# SCH_Mini_Fridge_Hat_2022-05-06.net
KiCad netlist of a schematic drawn in EasyEDA
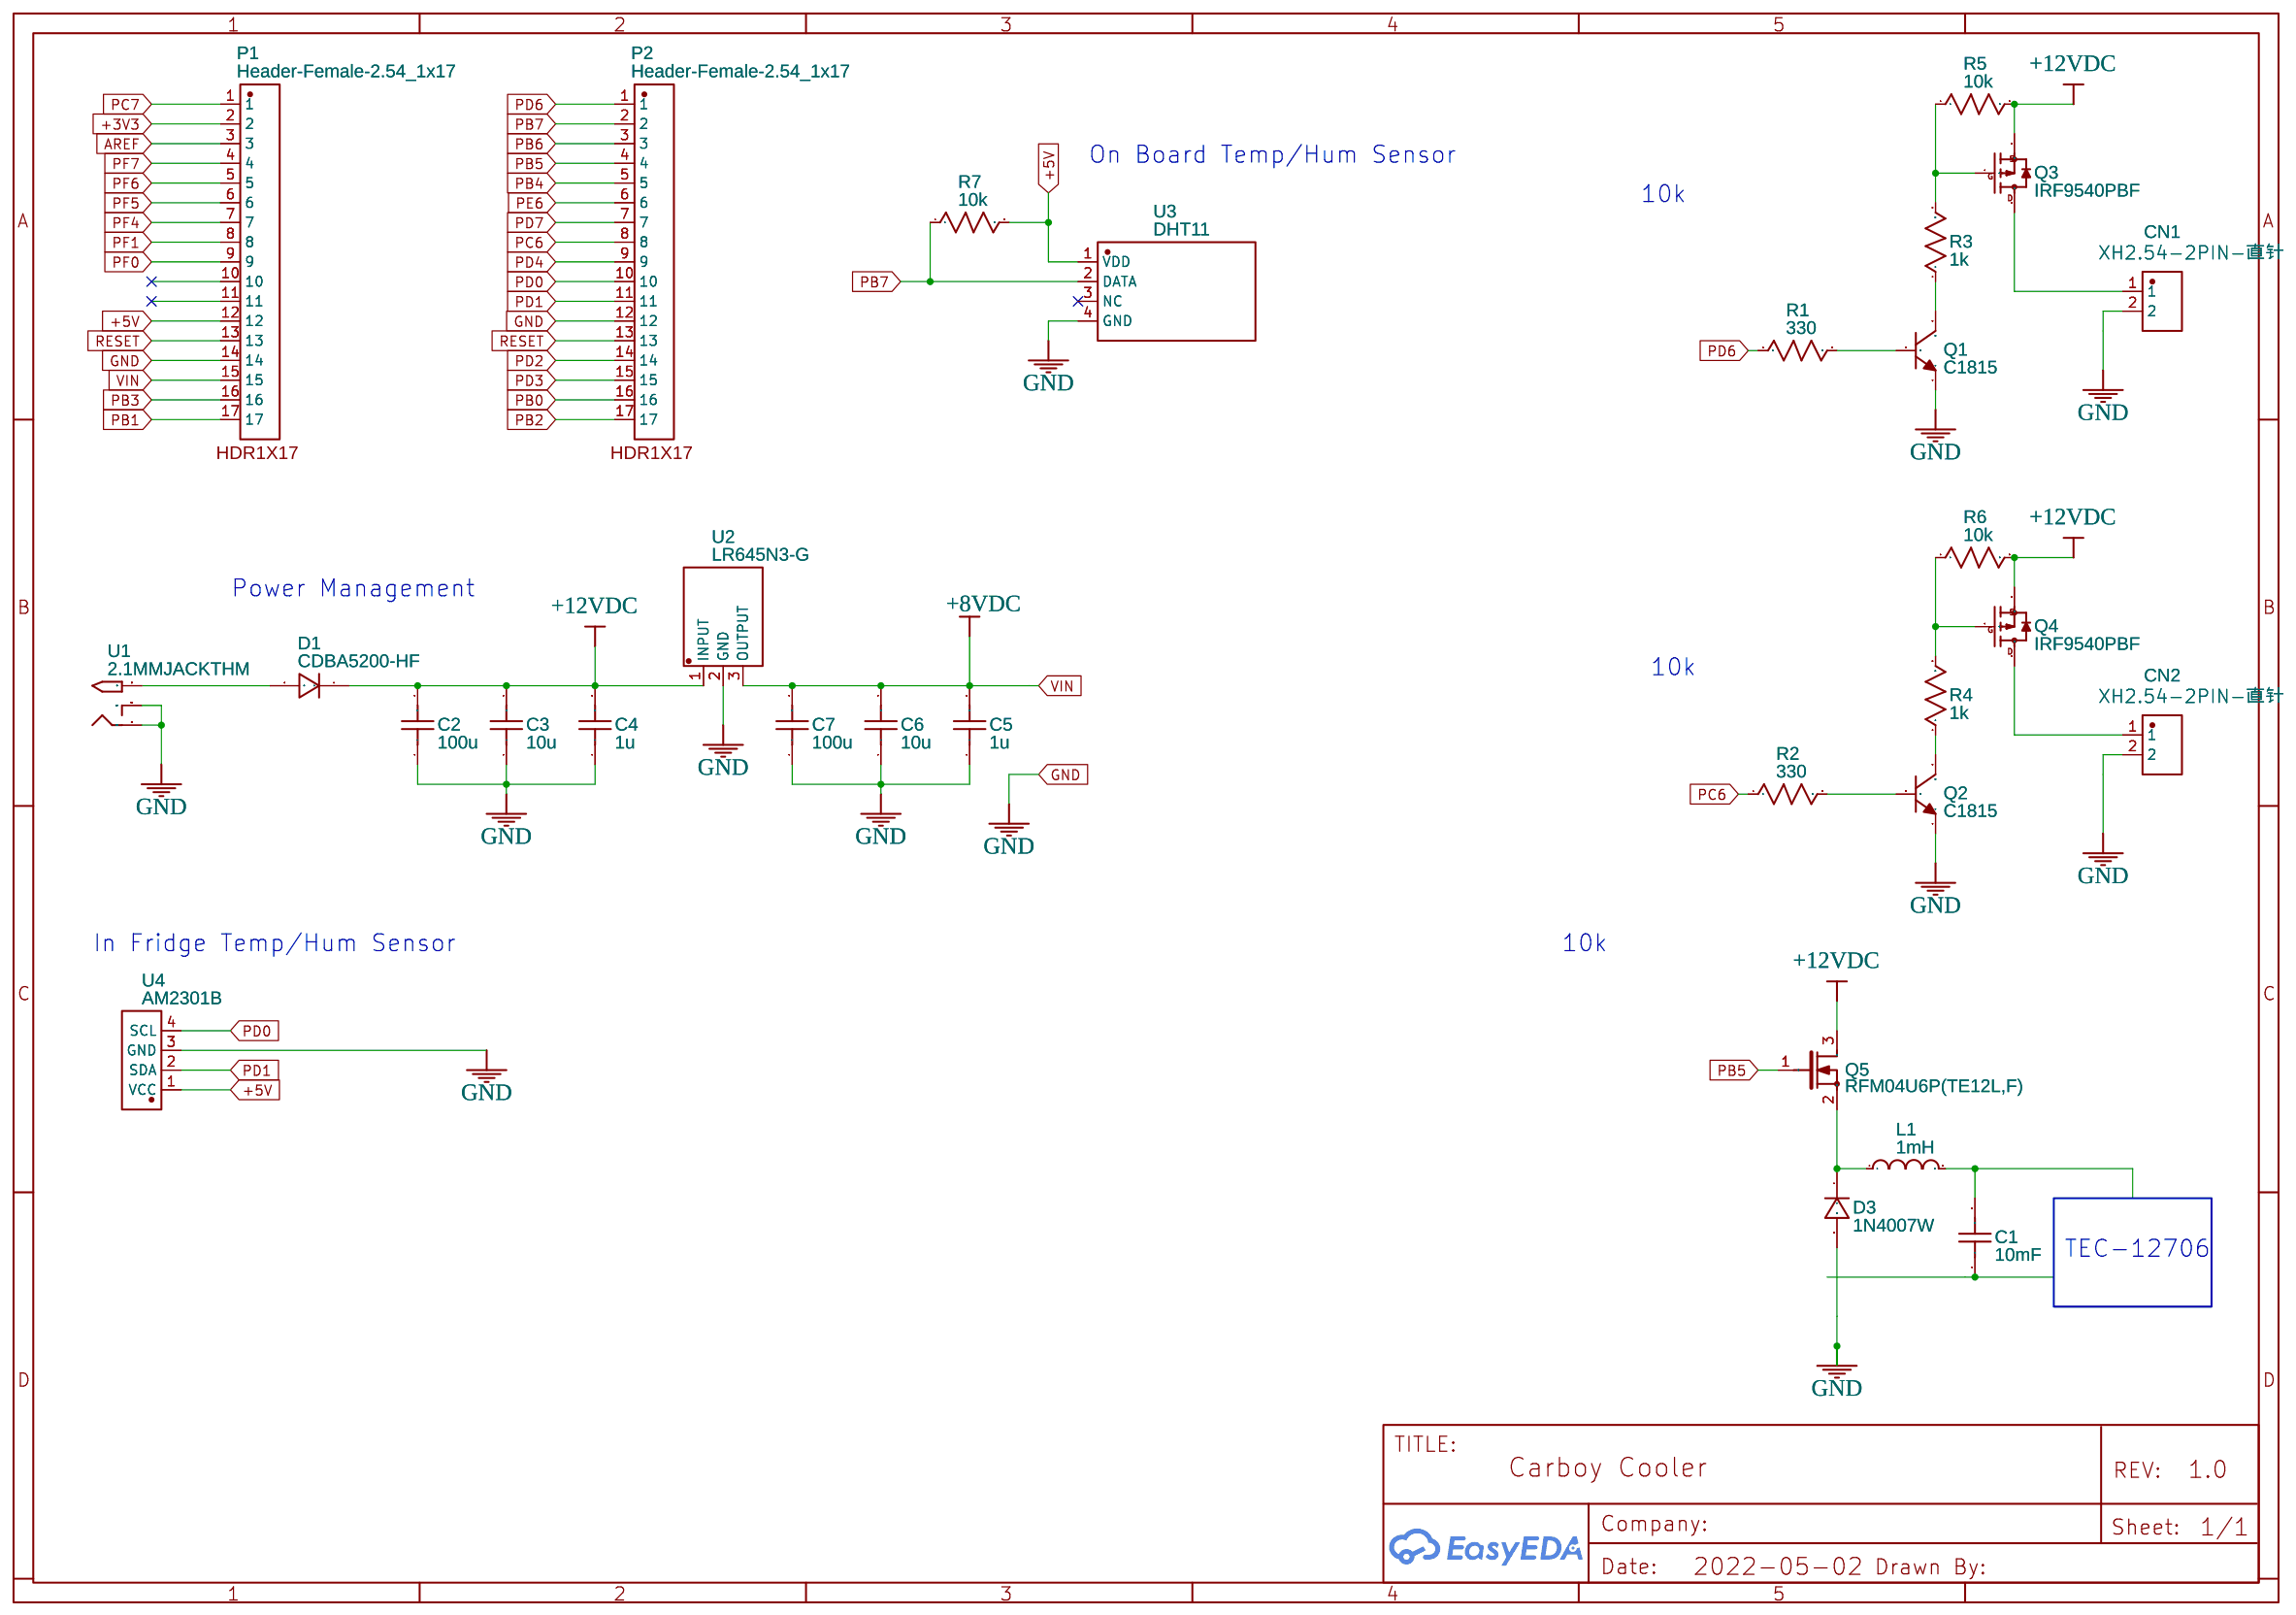
[diagram p0: schematic sheet]

(export (version "E")
  (design (tool "Eeschema 10.0.6"))
  (components
    (comp (ref "C1") (value "10mF") (libsource (lib "") (part "C_0805_US")))
    (comp (ref "C2") (value "100u") (libsource (lib "") (part "C_0805_US")))
    (comp (ref "C3") (value "10u") (libsource (lib "") (part "C_0805_US")))
    (comp (ref "C4") (value "1u") (libsource (lib "") (part "C_0805_US")))
    (comp (ref "C5") (value "1u") (libsource (lib "") (part "C_0805_US")))
    (comp (ref "C6") (value "10u") (libsource (lib "") (part "C_0805_US")))
    (comp (ref "C7") (value "100u") (libsource (lib "") (part "C_0805_US")))
    (comp (ref "CN1")
      (value "XH2.54-2PIN-直针")
      (fields (field (name "BOM_Supplier Part") "C9900011425"))
      (libsource (lib "") (part "XH2.54-2PIN-直针"))
    )
    (comp (ref "CN2")
      (value "XH2.54-2PIN-直针")
      (fields (field (name "BOM_Supplier Part") "C9900011425"))
      (libsource (lib "") (part "XH2.54-2PIN-直针"))
    )
    (comp (ref "D1")
      (value "CDBA5200-HF")
      (fields (field (name "BOM_Supplier Part") "641-1706-1-ND"))
      (libsource (lib "") (part "1N4007W_1"))
    )
    (comp (ref "D3")
      (value "1N4007W")
      (fields (field (name "BOM_Supplier Part") "C328592"))
      (libsource (lib "") (part "1N4007W"))
    )
    (comp (ref "L1") (value "1mH") (libsource (lib "") (part "L0603_US")))
    (comp (ref "P1") (value "Header-Female-2.54_1x17") (libsource (lib "") (part "17 Pin Header")))
    (comp (ref "P2") (value "Header-Female-2.54_1x17") (libsource (lib "") (part "17 Pin Header")))
    (comp (ref "Q1")
      (value "C1815")
      (fields (field (name "BOM_Supplier Part") "C57616"))
      (libsource (lib "") (part "C1815"))
    )
    (comp (ref "Q2")
      (value "C1815")
      (fields (field (name "BOM_Supplier Part") "C57616"))
      (libsource (lib "") (part "C1815"))
    )
    (comp (ref "Q3")
      (value "IRF9540PBF")
      (fields (field (name "BOM_Supplier Part") "C183014"))
      (libsource (lib "") (part "IRF9540PBF"))
    )
    (comp (ref "Q4")
      (value "IRF9540PBF")
      (fields (field (name "BOM_Supplier Part") "C183014"))
      (libsource (lib "") (part "IRF9540PBF"))
    )
    (comp (ref "Q5")
      (value "RFM04U6P(TE12L,F)")
      (fields (field (name "BOM_Supplier Part") "C194959"))
      (libsource (lib "") (part "RFM04U6P(TE12L,F)"))
    )
    (comp (ref "R1") (value "330") (libsource (lib "") (part "R_0805_US")))
    (comp (ref "R2") (value "330") (libsource (lib "") (part "R_0805_US")))
    (comp (ref "R3") (value "1k") (libsource (lib "") (part "R_0805_US_1")))
    (comp (ref "R4") (value "1k") (libsource (lib "") (part "R_0805_US_1")))
    (comp (ref "R5") (value "10k") (libsource (lib "") (part "R_0805_US")))
    (comp (ref "R6") (value "10k") (libsource (lib "") (part "R_0805_US")))
    (comp (ref "R7") (value "10k") (libsource (lib "") (part "R_0805_US")))
    (comp (ref "U1")
      (value "2.1MMJACKTHM")
      (fields (field (name "BOM_Supplier Part") "PJ-002AH"))
      (libsource (lib "") (part "2.1MMJACKTHM"))
    )
    (comp (ref "U2")
      (value "LR645N3-G")
      (fields (field (name "BOM_Supplier Part") "C184943"))
      (libsource (lib "") (part "LR645N3-G"))
    )
    (comp (ref "U3")
      (value "DHT11")
      (fields (field (name "BOM_Supplier Part") "C117051"))
      (libsource (lib "") (part "DHT11"))
    )
    (comp (ref "U4") (value "AM2301B") (libsource (lib "") (part "AM2301B")))
  )
  (nets
    (net (code "1") (name "+3V3") (class "Default")
      (node (ref "P1") (pin "2") (pinfunction "2_2") (pintype "unspecified"))
    )
    (net (code "2") (name "+5V") (class "Default")
      (node (ref "P1") (pin "12") (pinfunction "12_12") (pintype "unspecified"))
      (node (ref "R7") (pin "2") (pinfunction "2_2") (pintype "unspecified"))
      (node (ref "U3") (pin "1") (pinfunction "VDD_1") (pintype "unspecified"))
      (node (ref "U4") (pin "1") (pinfunction "VCC_1") (pintype "unspecified"))
    )
    (net (code "3") (name "+12VDC") (class "Default")
      (node (ref "C2") (pin "2") (pinfunction "2_2") (pintype "unspecified"))
      (node (ref "C3") (pin "2") (pinfunction "2_2") (pintype "unspecified"))
      (node (ref "C4") (pin "2") (pinfunction "2_2") (pintype "unspecified"))
      (node (ref "D1") (pin "1") (pinfunction "1_1") (pintype "unspecified"))
      (node (ref "Q3") (pin "3") (pinfunction "S_3") (pintype "unspecified"))
      (node (ref "Q4") (pin "3") (pinfunction "S_3") (pintype "unspecified"))
      (node (ref "Q5") (pin "3") (pinfunction "D_3") (pintype "unspecified"))
      (node (ref "R5") (pin "2") (pinfunction "2_2") (pintype "unspecified"))
      (node (ref "R6") (pin "2") (pinfunction "2_2") (pintype "unspecified"))
      (node (ref "U2") (pin "1") (pinfunction "INPUT_1") (pintype "unspecified"))
    )
    (net (code "4") (name "AREF") (class "Default")
      (node (ref "P1") (pin "3") (pinfunction "3_3") (pintype "unspecified"))
    )
    (net (code "5") (name "GND") (class "Default")
      (node (ref "C2") (pin "1") (pinfunction "1_1") (pintype "unspecified"))
      (node (ref "C3") (pin "1") (pinfunction "1_1") (pintype "unspecified"))
      (node (ref "C4") (pin "1") (pinfunction "1_1") (pintype "unspecified"))
      (node (ref "C5") (pin "1") (pinfunction "1_1") (pintype "unspecified"))
      (node (ref "C6") (pin "1") (pinfunction "1_1") (pintype "unspecified"))
      (node (ref "C7") (pin "1") (pinfunction "1_1") (pintype "unspecified"))
      (node (ref "CN1") (pin "2") (pinfunction "2_2") (pintype "unspecified"))
      (node (ref "CN2") (pin "2") (pinfunction "2_2") (pintype "unspecified"))
      (node (ref "D3") (pin "2") (pinfunction "2_2") (pintype "unspecified"))
      (node (ref "P1") (pin "14") (pinfunction "14_14") (pintype "unspecified"))
      (node (ref "P2") (pin "12") (pinfunction "12_12") (pintype "unspecified"))
      (node (ref "Q1") (pin "1") (pinfunction "E_1") (pintype "unspecified"))
      (node (ref "Q2") (pin "1") (pinfunction "E_1") (pintype "unspecified"))
      (node (ref "U1") (pin "RING") (pinfunction "RING_RING") (pintype "unspecified"))
      (node (ref "U1") (pin "RING_SW") (pinfunction "RING_SW_RING_SW") (pintype "unspecified"))
      (node (ref "U2") (pin "2") (pinfunction "GND_2") (pintype "unspecified"))
      (node (ref "U3") (pin "4") (pinfunction "GND_4") (pintype "unspecified"))
      (node (ref "U4") (pin "3") (pinfunction "GND_3") (pintype "unspecified"))
    )
    (net (code "6") (name "Net-(C1-Pad2)") (class "Default")
      (node (ref "C1") (pin "2") (pinfunction "2_2") (pintype "unspecified"))
      (node (ref "L1") (pin "2") (pinfunction "2_2") (pintype "unspecified"))
    )
    (net (code "7") (name "Net-(D1-Pad2)") (class "Default")
      (node (ref "D1") (pin "2") (pinfunction "2_2") (pintype "unspecified"))
      (node (ref "U1") (pin "TIP") (pinfunction "TIP_TIP") (pintype "unspecified"))
    )
    (net (code "8") (name "Net-(Q1-B)") (class "Default")
      (node (ref "Q1") (pin "3") (pinfunction "B_3") (pintype "unspecified"))
      (node (ref "R1") (pin "2") (pinfunction "2_2") (pintype "unspecified"))
    )
    (net (code "9") (name "Net-(Q1-C)") (class "Default")
      (node (ref "Q1") (pin "2") (pinfunction "C_2") (pintype "unspecified"))
      (node (ref "R3") (pin "1") (pinfunction "1_1") (pintype "unspecified"))
    )
    (net (code "10") (name "Net-(Q2-B)") (class "Default")
      (node (ref "Q2") (pin "3") (pinfunction "B_3") (pintype "unspecified"))
      (node (ref "R2") (pin "2") (pinfunction "2_2") (pintype "unspecified"))
    )
    (net (code "11") (name "Net-(Q2-C)") (class "Default")
      (node (ref "Q2") (pin "2") (pinfunction "C_2") (pintype "unspecified"))
      (node (ref "R4") (pin "1") (pinfunction "1_1") (pintype "unspecified"))
    )
    (net (code "12") (name "Net-(Q3-D)") (class "Default")
      (node (ref "CN1") (pin "1") (pinfunction "1_1") (pintype "unspecified"))
      (node (ref "Q3") (pin "2") (pinfunction "D_2") (pintype "unspecified"))
    )
    (net (code "13") (name "Net-(Q3-G)") (class "Default")
      (node (ref "Q3") (pin "1") (pinfunction "G_1") (pintype "unspecified"))
      (node (ref "R3") (pin "2") (pinfunction "2_2") (pintype "unspecified"))
      (node (ref "R5") (pin "1") (pinfunction "1_1") (pintype "unspecified"))
    )
    (net (code "14") (name "Net-(Q4-D)") (class "Default")
      (node (ref "CN2") (pin "1") (pinfunction "1_1") (pintype "unspecified"))
      (node (ref "Q4") (pin "2") (pinfunction "D_2") (pintype "unspecified"))
    )
    (net (code "15") (name "Net-(Q4-G)") (class "Default")
      (node (ref "Q4") (pin "1") (pinfunction "G_1") (pintype "unspecified"))
      (node (ref "R4") (pin "2") (pinfunction "2_2") (pintype "unspecified"))
      (node (ref "R6") (pin "1") (pinfunction "1_1") (pintype "unspecified"))
    )
    (net (code "16") (name "Net-(Q5-S)") (class "Default")
      (node (ref "D3") (pin "1") (pinfunction "1_1") (pintype "unspecified"))
      (node (ref "L1") (pin "1") (pinfunction "1_1") (pintype "unspecified"))
      (node (ref "Q5") (pin "2") (pinfunction "S_2") (pintype "unspecified"))
    )
    (net (code "17") (name "PB0") (class "Default")
      (node (ref "P2") (pin "16") (pinfunction "16_16") (pintype "unspecified"))
    )
    (net (code "18") (name "PB1") (class "Default")
      (node (ref "P1") (pin "17") (pinfunction "17_17") (pintype "unspecified"))
    )
    (net (code "19") (name "PB2") (class "Default")
      (node (ref "P2") (pin "17") (pinfunction "17_17") (pintype "unspecified"))
    )
    (net (code "20") (name "PB3") (class "Default")
      (node (ref "P1") (pin "16") (pinfunction "16_16") (pintype "unspecified"))
    )
    (net (code "21") (name "PB4") (class "Default")
      (node (ref "P2") (pin "5") (pinfunction "5_5") (pintype "unspecified"))
    )
    (net (code "22") (name "PB5") (class "Default")
      (node (ref "P2") (pin "4") (pinfunction "4_4") (pintype "unspecified"))
      (node (ref "Q5") (pin "1") (pinfunction "G_1") (pintype "unspecified"))
    )
    (net (code "23") (name "PB6") (class "Default")
      (node (ref "P2") (pin "3") (pinfunction "3_3") (pintype "unspecified"))
    )
    (net (code "24") (name "PB7") (class "Default")
      (node (ref "P2") (pin "2") (pinfunction "2_2") (pintype "unspecified"))
      (node (ref "R7") (pin "1") (pinfunction "1_1") (pintype "unspecified"))
      (node (ref "U3") (pin "2") (pinfunction "DATA_2") (pintype "unspecified"))
    )
    (net (code "25") (name "PC6") (class "Default")
      (node (ref "P2") (pin "8") (pinfunction "8_8") (pintype "unspecified"))
      (node (ref "R2") (pin "1") (pinfunction "1_1") (pintype "unspecified"))
    )
    (net (code "26") (name "PC7") (class "Default")
      (node (ref "P1") (pin "1") (pinfunction "1_1") (pintype "unspecified"))
    )
    (net (code "27") (name "PD0") (class "Default")
      (node (ref "P2") (pin "10") (pinfunction "10_10") (pintype "unspecified"))
      (node (ref "U4") (pin "4") (pinfunction "SCL_4") (pintype "unspecified"))
    )
    (net (code "28") (name "PD1") (class "Default")
      (node (ref "P2") (pin "11") (pinfunction "11_11") (pintype "unspecified"))
      (node (ref "U4") (pin "2") (pinfunction "SDA_2") (pintype "unspecified"))
    )
    (net (code "29") (name "PD2") (class "Default")
      (node (ref "P2") (pin "14") (pinfunction "14_14") (pintype "unspecified"))
    )
    (net (code "30") (name "PD3") (class "Default")
      (node (ref "P2") (pin "15") (pinfunction "15_15") (pintype "unspecified"))
    )
    (net (code "31") (name "PD4") (class "Default")
      (node (ref "P2") (pin "9") (pinfunction "9_9") (pintype "unspecified"))
    )
    (net (code "32") (name "PD6") (class "Default")
      (node (ref "P2") (pin "1") (pinfunction "1_1") (pintype "unspecified"))
      (node (ref "R1") (pin "1") (pinfunction "1_1") (pintype "unspecified"))
    )
    (net (code "33") (name "PD7") (class "Default")
      (node (ref "P2") (pin "7") (pinfunction "7_7") (pintype "unspecified"))
    )
    (net (code "34") (name "PE6") (class "Default")
      (node (ref "P2") (pin "6") (pinfunction "6_6") (pintype "unspecified"))
    )
    (net (code "35") (name "PF0") (class "Default")
      (node (ref "P1") (pin "9") (pinfunction "9_9") (pintype "unspecified"))
    )
    (net (code "36") (name "PF1") (class "Default")
      (node (ref "P1") (pin "8") (pinfunction "8_8") (pintype "unspecified"))
    )
    (net (code "37") (name "PF4") (class "Default")
      (node (ref "P1") (pin "7") (pinfunction "7_7") (pintype "unspecified"))
    )
    (net (code "38") (name "PF5") (class "Default")
      (node (ref "P1") (pin "6") (pinfunction "6_6") (pintype "unspecified"))
    )
    (net (code "39") (name "PF6") (class "Default")
      (node (ref "P1") (pin "5") (pinfunction "5_5") (pintype "unspecified"))
    )
    (net (code "40") (name "PF7") (class "Default")
      (node (ref "P1") (pin "4") (pinfunction "4_4") (pintype "unspecified"))
    )
    (net (code "41") (name "RESET") (class "Default")
      (node (ref "P1") (pin "13") (pinfunction "13_13") (pintype "unspecified"))
      (node (ref "P2") (pin "13") (pinfunction "13_13") (pintype "unspecified"))
    )
    (net (code "42") (name "VIN") (class "Default")
      (node (ref "C5") (pin "2") (pinfunction "2_2") (pintype "unspecified"))
      (node (ref "C6") (pin "2") (pinfunction "2_2") (pintype "unspecified"))
      (node (ref "C7") (pin "2") (pinfunction "2_2") (pintype "unspecified"))
      (node (ref "P1") (pin "15") (pinfunction "15_15") (pintype "unspecified"))
      (node (ref "U2") (pin "3") (pinfunction "OUTPUT_3") (pintype "unspecified"))
    )
    (net (code "43") (name "unconnected-(C1-Pad1)") (class "Default")
      (node (ref "C1") (pin "1") (pinfunction "1_1") (pintype "unspecified"))
    )
    (net (code "44") (name "unconnected-(P1-Pad10)") (class "Default")
      (node (ref "P1") (pin "10") (pinfunction "10_10") (pintype "unspecified+no_connect"))
    )
    (net (code "45") (name "unconnected-(P1-Pad11)") (class "Default")
      (node (ref "P1") (pin "11") (pinfunction "11_11") (pintype "unspecified+no_connect"))
    )
    (net (code "46") (name "unconnected-(U3-NC-Pad3)") (class "Default")
      (node (ref "U3") (pin "3") (pinfunction "NC_3") (pintype "unspecified+no_connect"))
    )
  )
)
